# Pluvion_2_-_Rev_C.net
KiCad netlist of a schematic drawn in EAGLE
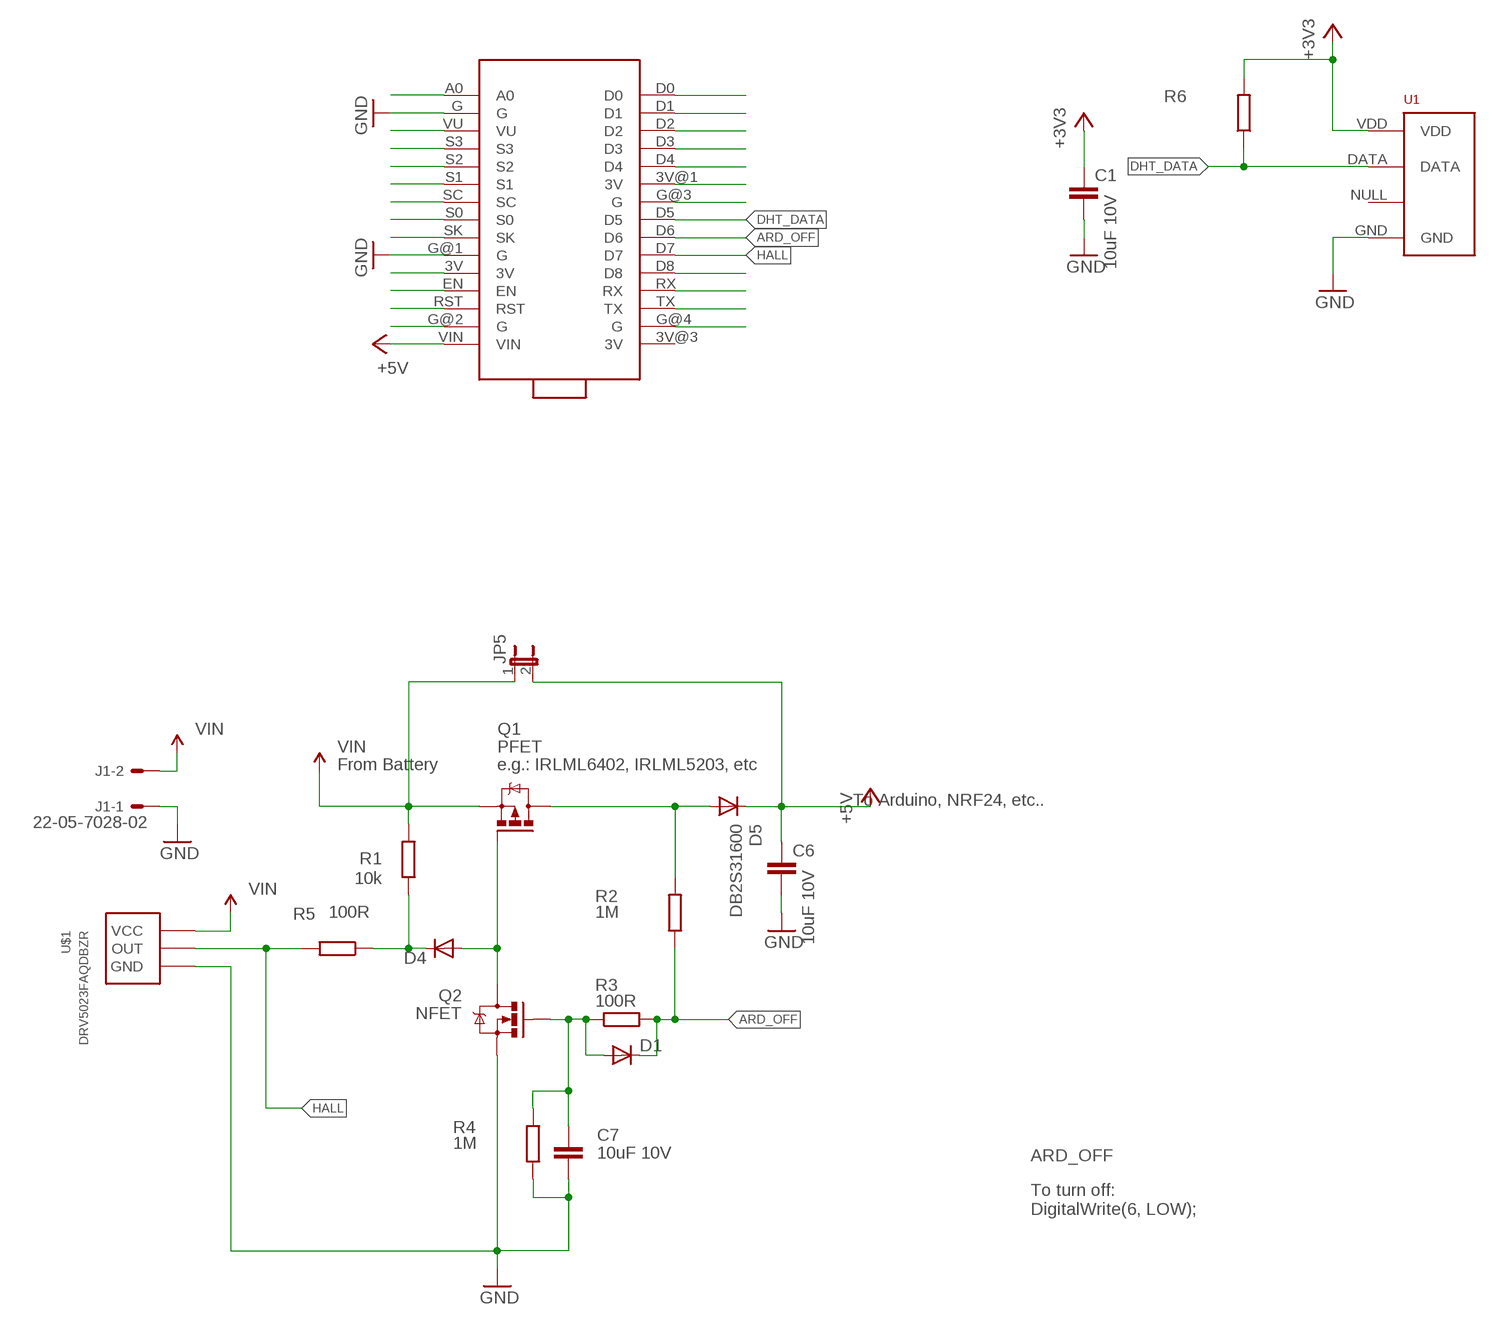
[diagram p0: schematic, sheet 1]

(export (version "E")
  (design (tool "Eeschema 10.0.6"))
  (components
    (comp (ref "C1")
      (value "10uF 10V")
      (footprint "eagle-import:C0805")
      (libsource (lib "eagle-import") (part "C-EUC0805"))
    )
    (comp (ref "C6")
      (value "10uF 10V")
      (footprint "eagle-import:C0805")
      (libsource (lib "eagle-import") (part "C-EUC0805"))
    )
    (comp (ref "C7")
      (value "10uF 10V")
      (footprint "eagle-import:C0805")
      (libsource (lib "eagle-import") (part "C-EUC0805"))
    )
    (comp (ref "D1")
      (value "DIODESOD")
      (footprint "eagle-import:SOD-323")
      (libsource (lib "eagle-import") (part "DIODESOD"))
    )
    (comp (ref "D4")
      (value "DIODESOD")
      (footprint "eagle-import:SOD-323")
      (libsource (lib "eagle-import") (part "DIODESOD"))
    )
    (comp (ref "D5")
      (value "DB2S31600")
      (footprint "eagle-import:SMA-DIODE")
      (libsource (lib "eagle-import") (part "DIODESMA"))
    )
    (comp (ref "J1")
      (value "22-05-7028-02")
      (footprint "eagle-import:7395-02")
      (libsource (lib "eagle-import") (part "22-?-0205-7028"))
    )
    (comp (ref "JP5")
      (value "JUMPER-2PTH")
      (footprint "eagle-import:1X02")
      (libsource (lib "eagle-import") (part "JUMPER-2PTH"))
    )
    (comp (ref "Q1")
      (value "PFET")
      (footprint "eagle-import:MICRO3")
      (libsource (lib "eagle-import") (part "IRLML5203"))
    )
    (comp (ref "Q2")
      (value "NFET")
      (footprint "eagle-import:SOT23")
      (libsource (lib "eagle-import") (part "MOSFET-NCHANNELBSS123LT1G"))
    )
    (comp (ref "R1")
      (value "10k")
      (footprint "eagle-import:R0805")
      (libsource (lib "eagle-import") (part "R-EU_R0805"))
    )
    (comp (ref "R2")
      (value "1M")
      (footprint "eagle-import:R0805")
      (libsource (lib "eagle-import") (part "R-EU_R0805"))
    )
    (comp (ref "R3")
      (value "100R")
      (footprint "eagle-import:R0805")
      (libsource (lib "eagle-import") (part "R-EU_R0805"))
    )
    (comp (ref "R4")
      (value "1M")
      (footprint "eagle-import:R0805")
      (libsource (lib "eagle-import") (part "R-EU_R0805"))
    )
    (comp (ref "R5")
      (value "100R")
      (footprint "eagle-import:R0805")
      (libsource (lib "eagle-import") (part "R-EU_R0805"))
    )
    (comp (ref "R6")
      (value "R-EU_R0805")
      (footprint "eagle-import:R0805")
      (libsource (lib "eagle-import") (part "R-EU_R0805"))
    )
    (comp (ref "U$1")
      (value "DRV5023FAQDBZR")
      (footprint "eagle-import:SOT23")
      (libsource (lib "eagle-import") (part "DRV5023FAQDBZR"))
    )
    (comp (ref "U$2")
      (value "NODE-LOLIN-ESP8266")
      (footprint "eagle-import:NODE-LOLIN-ESP8266")
      (libsource (lib "eagle-import") (part "NODE-LOLIN-ESP8266"))
    )
    (comp (ref "U1")
      (value "RHT03_DHT-22_AM2302RA")
      (footprint "eagle-import:RHT03_DHT-22_RA")
      (libsource (lib "eagle-import") (part "RHT03_DHT-22_AM2302RA"))
    )
  )
  (nets
    (net (code "1") (name "+3V3") (class "Default")
      (node (ref "C1") (pin "1") (pinfunction "1_1") (pintype "passive"))
      (node (ref "R6") (pin "2") (pinfunction "2_2") (pintype "passive"))
      (node (ref "U$2") (pin "3V@1") (pinfunction "3V_3V@1") (pintype "bidirectional"))
      (node (ref "U1") (pin "VDD") (pinfunction "VDD_VDD") (pintype "power_in"))
    )
    (net (code "2") (name "+5V") (class "Default")
      (node (ref "C6") (pin "1") (pinfunction "1_1") (pintype "passive"))
      (node (ref "D5") (pin "C") (pinfunction "C_C") (pintype "passive"))
      (node (ref "JP5") (pin "2") (pinfunction "2_2") (pintype "passive"))
      (node (ref "U$2") (pin "VIN") (pinfunction "VIN_VIN") (pintype "bidirectional"))
    )
    (net (code "3") (name "ARD_OFF") (class "Default")
      (node (ref "D1") (pin "1") (pinfunction "C_1") (pintype "passive"))
      (node (ref "R2") (pin "1") (pinfunction "1_1") (pintype "passive"))
      (node (ref "R3") (pin "2") (pinfunction "2_2") (pintype "passive"))
      (node (ref "U$2") (pin "D6") (pinfunction "D6_D6") (pintype "bidirectional"))
    )
    (net (code "4") (name "DHT_DATA") (class "Default")
      (node (ref "R6") (pin "1") (pinfunction "1_1") (pintype "passive"))
      (node (ref "U$2") (pin "D5") (pinfunction "D5_D5") (pintype "bidirectional"))
      (node (ref "U1") (pin "DATA") (pinfunction "DATA_DATA") (pintype "bidirectional"))
    )
    (net (code "5") (name "GND") (class "Default")
      (node (ref "C1") (pin "2") (pinfunction "2_2") (pintype "passive"))
      (node (ref "C6") (pin "2") (pinfunction "2_2") (pintype "passive"))
      (node (ref "C7") (pin "2") (pinfunction "2_2") (pintype "passive"))
      (node (ref "J1") (pin "1") (pinfunction "S_1") (pintype "passive"))
      (node (ref "Q2") (pin "2") (pinfunction "S_2") (pintype "passive"))
      (node (ref "R4") (pin "1") (pinfunction "1_1") (pintype "passive"))
      (node (ref "U$1") (pin "3") (pinfunction "GND_3") (pintype "bidirectional"))
      (node (ref "U$2") (pin "G") (pinfunction "G_G") (pintype "bidirectional"))
      (node (ref "U$2") (pin "G@1") (pinfunction "G_G@1") (pintype "bidirectional"))
      (node (ref "U1") (pin "GND") (pinfunction "GND_GND") (pintype "power_in"))
    )
    (net (code "6") (name "HALL") (class "Default")
      (node (ref "R5") (pin "2") (pinfunction "2_2") (pintype "passive"))
      (node (ref "U$1") (pin "2") (pinfunction "OUT_2") (pintype "bidirectional"))
      (node (ref "U$2") (pin "D7") (pinfunction "D7_D7") (pintype "bidirectional"))
    )
    (net (code "7") (name "Net-(D1-A)") (class "Default")
      (node (ref "C7") (pin "1") (pinfunction "1_1") (pintype "passive"))
      (node (ref "D1") (pin "2") (pinfunction "A_2") (pintype "passive"))
      (node (ref "Q2") (pin "1") (pinfunction "G_1") (pintype "passive"))
      (node (ref "R3") (pin "1") (pinfunction "1_1") (pintype "passive"))
      (node (ref "R4") (pin "2") (pinfunction "2_2") (pintype "passive"))
    )
    (net (code "8") (name "Net-(D4-A)") (class "Default")
      (node (ref "D4") (pin "2") (pinfunction "A_2") (pintype "passive"))
      (node (ref "Q1") (pin "1") (pinfunction "G_1") (pintype "passive"))
      (node (ref "Q2") (pin "3") (pinfunction "D_3") (pintype "passive"))
    )
    (net (code "9") (name "Net-(D4-C)") (class "Default")
      (node (ref "D4") (pin "1") (pinfunction "C_1") (pintype "passive"))
      (node (ref "R1") (pin "1") (pinfunction "1_1") (pintype "passive"))
      (node (ref "R5") (pin "1") (pinfunction "1_1") (pintype "passive"))
    )
    (net (code "10") (name "Net-(Q1-D)") (class "Default")
      (node (ref "D5") (pin "A") (pinfunction "A_A") (pintype "passive"))
      (node (ref "Q1") (pin "3") (pinfunction "D_3") (pintype "passive"))
      (node (ref "R2") (pin "2") (pinfunction "2_2") (pintype "passive"))
    )
    (net (code "11") (name "VIN") (class "Default")
      (node (ref "J1") (pin "2") (pinfunction "S_2") (pintype "passive"))
      (node (ref "JP5") (pin "1") (pinfunction "1_1") (pintype "passive"))
      (node (ref "Q1") (pin "2") (pinfunction "S_2") (pintype "passive"))
      (node (ref "R1") (pin "2") (pinfunction "2_2") (pintype "passive"))
      (node (ref "U$1") (pin "1") (pinfunction "VCC_1") (pintype "bidirectional"))
    )
    (net (code "12") (name "unconnected-(U$2-3V-Pad3V@3)") (class "Default")
      (node (ref "U$2") (pin "3V@3") (pinfunction "3V_3V@3") (pintype "bidirectional"))
    )
    (net (code "13") (name "unconnected-(U$2-G-PadG@2)") (class "Default")
      (node (ref "U$2") (pin "G@2") (pinfunction "G_G@2") (pintype "bidirectional"))
    )
    (net (code "14") (name "unconnected-(U$2-G-PadG@3)") (class "Default")
      (node (ref "U$2") (pin "G@3") (pinfunction "G_G@3") (pintype "bidirectional"))
    )
    (net (code "15") (name "unconnected-(U$2-G-PadG@4)") (class "Default")
      (node (ref "U$2") (pin "G@4") (pinfunction "G_G@4") (pintype "bidirectional"))
    )
    (net (code "16") (name "unconnected-(U$2-Pad3V)") (class "Default")
      (node (ref "U$2") (pin "3V") (pinfunction "3V_3V") (pintype "bidirectional"))
    )
    (net (code "17") (name "unconnected-(U$2-PadA0)") (class "Default")
      (node (ref "U$2") (pin "A0") (pinfunction "A0_A0") (pintype "bidirectional"))
    )
    (net (code "18") (name "unconnected-(U$2-PadD0)") (class "Default")
      (node (ref "U$2") (pin "D0") (pinfunction "D0_D0") (pintype "bidirectional"))
    )
    (net (code "19") (name "unconnected-(U$2-PadD1)") (class "Default")
      (node (ref "U$2") (pin "D1") (pinfunction "D1_D1") (pintype "bidirectional"))
    )
    (net (code "20") (name "unconnected-(U$2-PadD2)") (class "Default")
      (node (ref "U$2") (pin "D2") (pinfunction "D2_D2") (pintype "bidirectional"))
    )
    (net (code "21") (name "unconnected-(U$2-PadD3)") (class "Default")
      (node (ref "U$2") (pin "D3") (pinfunction "D3_D3") (pintype "bidirectional"))
    )
    (net (code "22") (name "unconnected-(U$2-PadD4)") (class "Default")
      (node (ref "U$2") (pin "D4") (pinfunction "D4_D4") (pintype "bidirectional"))
    )
    (net (code "23") (name "unconnected-(U$2-PadD8)") (class "Default")
      (node (ref "U$2") (pin "D8") (pinfunction "D8_D8") (pintype "bidirectional"))
    )
    (net (code "24") (name "unconnected-(U$2-PadEN)") (class "Default")
      (node (ref "U$2") (pin "EN") (pinfunction "EN_EN") (pintype "bidirectional"))
    )
    (net (code "25") (name "unconnected-(U$2-PadRST)") (class "Default")
      (node (ref "U$2") (pin "RST") (pinfunction "RST_RST") (pintype "bidirectional"))
    )
    (net (code "26") (name "unconnected-(U$2-PadRX)") (class "Default")
      (node (ref "U$2") (pin "RX") (pinfunction "RX_RX") (pintype "bidirectional"))
    )
    (net (code "27") (name "unconnected-(U$2-PadS0)") (class "Default")
      (node (ref "U$2") (pin "S0") (pinfunction "S0_S0") (pintype "bidirectional"))
    )
    (net (code "28") (name "unconnected-(U$2-PadS1)") (class "Default")
      (node (ref "U$2") (pin "S1") (pinfunction "S1_S1") (pintype "bidirectional"))
    )
    (net (code "29") (name "unconnected-(U$2-PadS2)") (class "Default")
      (node (ref "U$2") (pin "S2") (pinfunction "S2_S2") (pintype "bidirectional"))
    )
    (net (code "30") (name "unconnected-(U$2-PadS3)") (class "Default")
      (node (ref "U$2") (pin "S3") (pinfunction "S3_S3") (pintype "bidirectional"))
    )
    (net (code "31") (name "unconnected-(U$2-PadSC)") (class "Default")
      (node (ref "U$2") (pin "SC") (pinfunction "SC_SC") (pintype "bidirectional"))
    )
    (net (code "32") (name "unconnected-(U$2-PadSK)") (class "Default")
      (node (ref "U$2") (pin "SK") (pinfunction "SK_SK") (pintype "bidirectional"))
    )
    (net (code "33") (name "unconnected-(U$2-PadTX)") (class "Default")
      (node (ref "U$2") (pin "TX") (pinfunction "TX_TX") (pintype "bidirectional"))
    )
    (net (code "34") (name "unconnected-(U$2-PadVU)") (class "Default")
      (node (ref "U$2") (pin "VU") (pinfunction "VU_VU") (pintype "bidirectional"))
    )
    (net (code "35") (name "unconnected-(U1-PadNULL)") (class "Default")
      (node (ref "U1") (pin "NULL") (pinfunction "NULL_NULL") (pintype "no_connect"))
    )
  )
)
